# 401_RPi0.net
KiCad netlist of a schematic drawn in Altium Designer
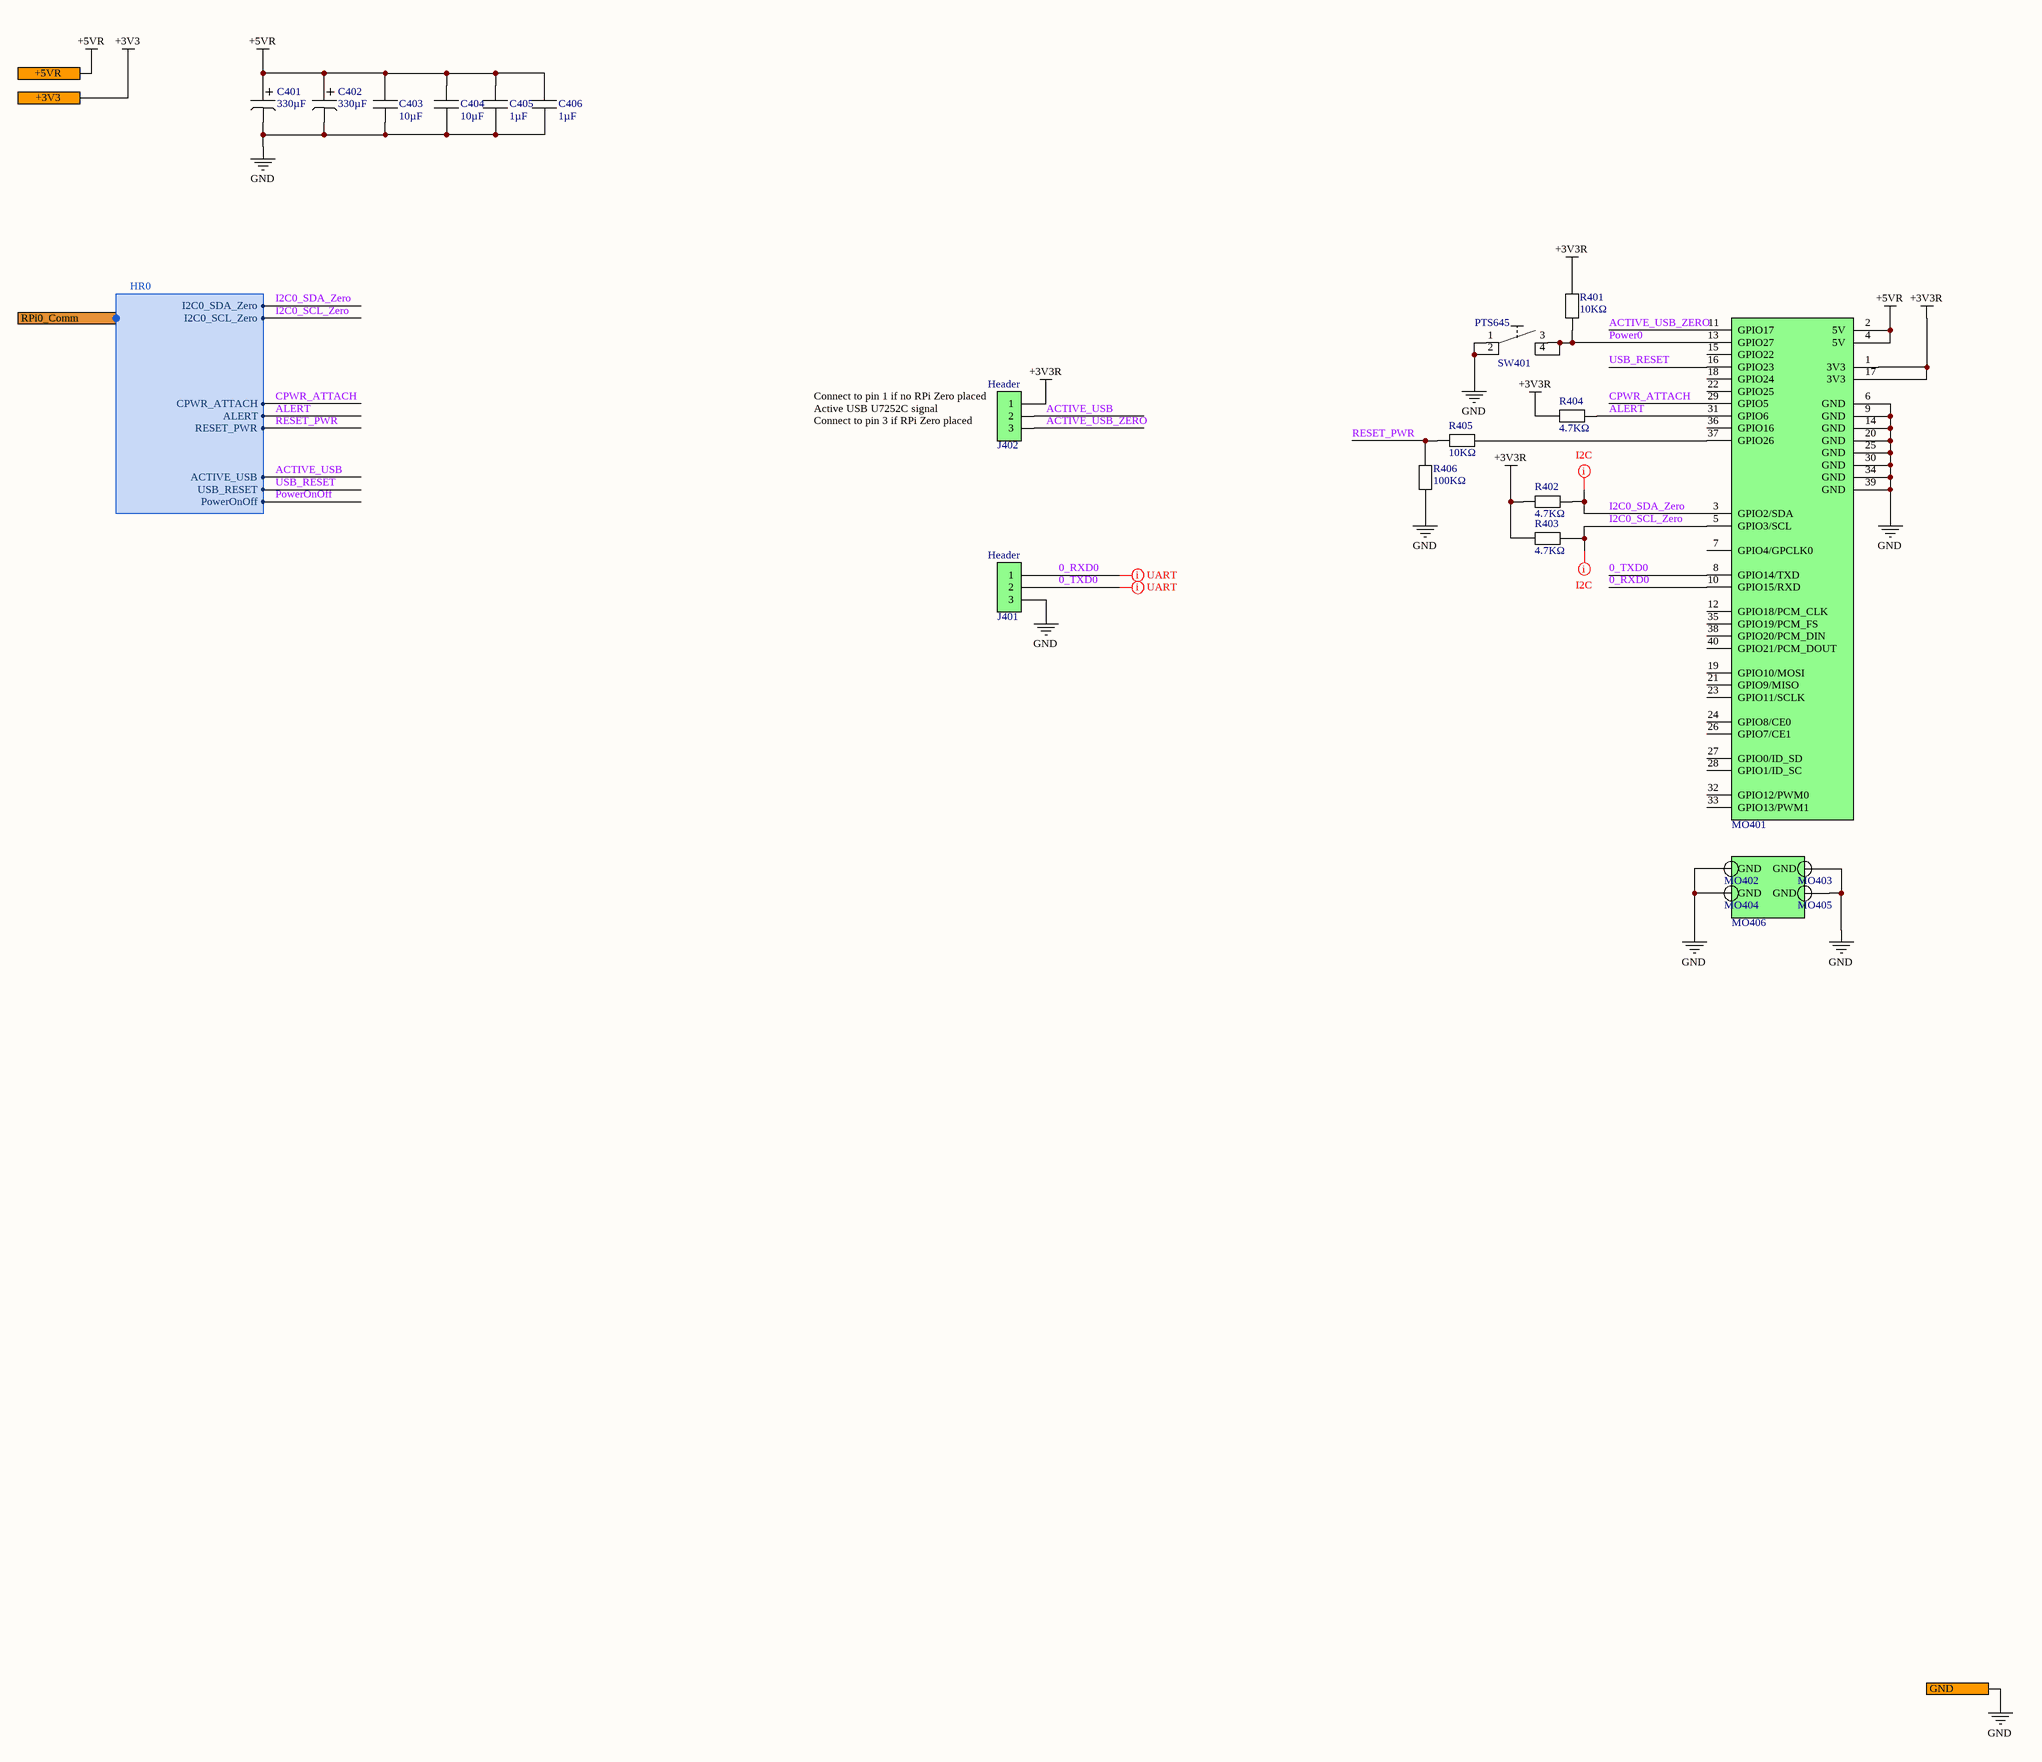
[diagram p0: 401_RPi0.SchDoc]

(export (version "E")
  (design (tool "Eeschema 10.0.6"))
  (components
    (comp (ref "C401")
      (value "330µF")
      (footprint "EC_E7")
      (description "330µF 16V 20% 16mΩ 4100mA")
      (fields
        (field (name "REFVAL") "330µF")
        (field (name "PART NUMBER") "CA0012")
        (field (name "MANFACTPART") "16SVPG330MX")
      )
      (libsource (lib "GTS_Database") (part "C+"))
    )
    (comp (ref "C402")
      (value "330µF")
      (footprint "EC_E7")
      (description "330µF 16V 20% 16mΩ 4100mA")
      (fields
        (field (name "REFVAL") "330µF")
        (field (name "PART NUMBER") "CA0012")
        (field (name "MANFACTPART") "16SVPG330MX")
      )
      (libsource (lib "GTS_Database") (part "C+"))
    )
    (comp (ref "C403")
      (value "10µF")
      (footprint "C0805")
      (description "10µF 16V 10% X5R")
      (fields
        (field (name "REFVAL") "10µF")
        (field (name "PART NUMBER") "CA0001")
        (field (name "MANFACTPART") "GRM21BR61C106KE15L")
      )
      (libsource (lib "GTS_Database") (part "C"))
    )
    (comp (ref "C404")
      (value "10µF")
      (footprint "C0805")
      (description "10µF 16V 10% X5R")
      (fields
        (field (name "REFVAL") "10µF")
        (field (name "PART NUMBER") "CA0001")
        (field (name "MANFACTPART") "GRM21BR61C106KE15L")
      )
      (libsource (lib "GTS_Database") (part "C"))
    )
    (comp (ref "C405")
      (value "1µF")
      (footprint "C0603")
      (description "1µF 16V 10% X5R")
      (fields
        (field (name "REFVAL") "1µF")
        (field (name "PART NUMBER") "CA0003")
        (field (name "MANFACTPART") "C1608X5R1C105K080AA")
      )
      (libsource (lib "GTS_Database") (part "C"))
    )
    (comp (ref "C406")
      (value "1µF")
      (footprint "C0603")
      (description "1µF 16V 10% X5R")
      (fields
        (field (name "REFVAL") "1µF")
        (field (name "PART NUMBER") "CA0003")
        (field (name "MANFACTPART") "C1608X5R1C105K080AA")
      )
      (libsource (lib "GTS_Database") (part "C"))
    )
    (comp (ref "J401")
      (value "Header")
      (footprint "1X3P_2.54mm")
      (description "Header 1x3P")
      (fields
        (field (name "REFVAL") "Header")
        (field (name "PART NUMBER") "CO0018")
        (field (name "MANFACTPART") "G800W305018EU")
      )
      (libsource (lib "GTS_Database") (part "CONN1X3P"))
    )
    (comp (ref "J402")
      (value "Header")
      (footprint "1X3P_2.54mm")
      (description "Header 1x3P")
      (fields
        (field (name "REFVAL") "Header")
        (field (name "PART NUMBER") "CO0018")
        (field (name "MANFACTPART") "G800W305018EU")
      )
      (libsource (lib "GTS_Database") (part "CONN1X3P"))
    )
    (comp (ref "MO401")
      (value "ZeroW-1")
      (footprint "RPIZeroW_HeaderPins")
      (description "RPI ZeroW Header 1-40")
      (fields (field (name "PART NUMBER") "MO0017") (field (name "MANFACTPART") "9900002236265"))
      (libsource (lib "GTS_Database") (part "RPIZeroW_Pins"))
    )
    (comp (ref "MO402")
      (value "ZeroW-M")
      (footprint "CM4-M")
      (description "RPI ZeroW Mounting Studs")
      (fields (field (name "PART NUMBER") "MO0016") (field (name "MANFACTPART") "9774030151R"))
      (libsource (lib "GTS_Database") (part "RPICM4_Mounting"))
    )
    (comp (ref "MO403")
      (value "ZeroW-M")
      (footprint "CM4-M")
      (description "RPI ZeroW Mounting Studs")
      (fields (field (name "PART NUMBER") "MO0016") (field (name "MANFACTPART") "9774030151R"))
      (libsource (lib "GTS_Database") (part "RPICM4_Mounting"))
    )
    (comp (ref "MO404")
      (value "ZeroW-M")
      (footprint "CM4-M")
      (description "RPI ZeroW Mounting Studs")
      (fields (field (name "PART NUMBER") "MO0016") (field (name "MANFACTPART") "9774030151R"))
      (libsource (lib "GTS_Database") (part "RPICM4_Mounting"))
    )
    (comp (ref "MO405")
      (value "ZeroW-M")
      (footprint "CM4-M")
      (description "RPI ZeroW Mounting Studs")
      (fields (field (name "PART NUMBER") "MO0016") (field (name "MANFACTPART") "9774030151R"))
      (libsource (lib "GTS_Database") (part "RPICM4_Mounting"))
    )
    (comp (ref "MO406")
      (value "ZeroW")
      (footprint "RPIZeroW_Layout_Heightened")
      (description "Outline of ZeroW Heigthened P\\lacement")
      (fields (field (name "PART NUMBER") "MO0022") (field (name "MANFACTPART") "RPI Zero W"))
      (libsource (lib "GTS_Database") (part "RPIZeroW_Layout"))
    )
    (comp (ref "R401")
      (value "10KΩ")
      (footprint "R0402")
      (description "10KΩ 1% 62.5mW")
      (fields
        (field (name "REFVAL") "10KΩ")
        (field (name "PART NUMBER") "RS0011")
        (field (name "MANFACTPART") "WR04X1002FTL")
      )
      (libsource (lib "GTS_Database") (part "R"))
    )
    (comp (ref "R402")
      (value "4.7KΩ")
      (footprint "R0603")
      (description "4.7KΩ 1% 100mW")
      (fields
        (field (name "REFVAL") "4.7KΩ")
        (field (name "PART NUMBER") "RS0002")
        (field (name "MANFACTPART") "WR06X4701FTL")
      )
      (libsource (lib "GTS_Database") (part "R"))
    )
    (comp (ref "R403")
      (value "4.7KΩ")
      (footprint "R0603")
      (description "4.7KΩ 1% 100mW")
      (fields
        (field (name "REFVAL") "4.7KΩ")
        (field (name "PART NUMBER") "RS0002")
        (field (name "MANFACTPART") "WR06X4701FTL")
      )
      (libsource (lib "GTS_Database") (part "R"))
    )
    (comp (ref "R404")
      (value "4.7KΩ")
      (footprint "R0603")
      (description "4.7KΩ 1% 100mW")
      (fields
        (field (name "REFVAL") "4.7KΩ")
        (field (name "PART NUMBER") "RS0002")
        (field (name "MANFACTPART") "WR06X4701FTL")
      )
      (libsource (lib "GTS_Database") (part "R"))
    )
    (comp (ref "R405")
      (value "10KΩ")
      (footprint "R0402")
      (description "10KΩ 1% 62.5mW")
      (fields
        (field (name "REFVAL") "10KΩ")
        (field (name "PART NUMBER") "RS0011")
        (field (name "MANFACTPART") "WR04X1002FTL")
      )
      (libsource (lib "GTS_Database") (part "R"))
    )
    (comp (ref "R406")
      (value "100KΩ")
      (footprint "R0402")
      (description "100KΩ 1% 62.5mW 100PPM")
      (fields
        (field (name "REFVAL") "100KΩ")
        (field (name "PART NUMBER") "RS0036")
        (field (name "MANFACTPART") "AC0402FR-13100KL")
      )
      (libsource (lib "GTS_Database") (part "R"))
    )
    (comp (ref "SW401")
      (value "PTS645")
      (footprint "PTS645-V")
      (description "TACTILE SWITCH SPST")
      (fields
        (field (name "REFVAL") "PTS645")
        (field (name "PART NUMBER") "SW0003")
        (field (name "MANFACTPART") "PTS645VK832LFS")
      )
      (libsource (lib "GTS_Database") (part "SPST-2-4"))
    )
  )
  (nets
    (net (code "3") (name "+3V3R") (class "Default")
      (node (ref "J402") (pin "1") (pinfunction "1_1") (pintype "passive"))
      (node (ref "MO401") (pin "1") (pinfunction "3V3_1") (pintype "passive"))
      (node (ref "MO401") (pin "17") (pinfunction "3V3_17") (pintype "passive"))
      (node (ref "R401") (pin "2") (pinfunction "2_2") (pintype "passive"))
      (node (ref "R402") (pin "1") (pinfunction "1_1") (pintype "passive"))
      (node (ref "R403") (pin "1") (pinfunction "1_1") (pintype "passive"))
      (node (ref "R404") (pin "1") (pinfunction "1_1") (pintype "passive"))
    )
    (net (code "4") (name "+5VR") (class "Default")
      (node (ref "C401") (pin "1") (pinfunction "1_1") (pintype "passive"))
      (node (ref "C402") (pin "1") (pinfunction "1_1") (pintype "passive"))
      (node (ref "C403") (pin "1") (pinfunction "1_1") (pintype "passive"))
      (node (ref "C404") (pin "1") (pinfunction "1_1") (pintype "passive"))
      (node (ref "C405") (pin "1") (pinfunction "1_1") (pintype "passive"))
      (node (ref "C406") (pin "1") (pinfunction "1_1") (pintype "passive"))
      (node (ref "MO401") (pin "2") (pinfunction "5V_2") (pintype "passive"))
      (node (ref "MO401") (pin "4") (pinfunction "5V_4") (pintype "passive"))
    )
    (net (code "5") (name "/0_RXD0") (class "Default")
      (node (ref "J401") (pin "1") (pinfunction "1_1") (pintype "passive"))
      (node (ref "MO401") (pin "10") (pinfunction "GPIO15/RXD_10") (pintype "passive"))
    )
    (net (code "6") (name "/0_TXD0") (class "Default")
      (node (ref "J401") (pin "2") (pinfunction "2_2") (pintype "passive"))
      (node (ref "MO401") (pin "8") (pinfunction "GPIO14/TXD_8") (pintype "passive"))
    )
    (net (code "7") (name "/ACTIVE_USB") (class "Default")
      (node (ref "J402") (pin "2") (pinfunction "2_2") (pintype "passive"))
    )
    (net (code "8") (name "/ACTIVE_USB_ZERO") (class "Default")
      (node (ref "J402") (pin "3") (pinfunction "3_3") (pintype "passive"))
      (node (ref "MO401") (pin "11") (pinfunction "GPIO17_11") (pintype "passive"))
    )
    (net (code "9") (name "/ALERT") (class "Default")
      (node (ref "MO401") (pin "31") (pinfunction "GPIO6_31") (pintype "passive"))
      (node (ref "R404") (pin "2") (pinfunction "2_2") (pintype "passive"))
    )
    (net (code "10") (name "/CPWR_ATTACH") (class "Default")
      (node (ref "MO401") (pin "29") (pinfunction "GPIO5_29") (pintype "passive"))
    )
    (net (code "11") (name "/I2C0_SCL_Zero") (class "Default")
      (node (ref "MO401") (pin "5") (pinfunction "GPIO3/SCL_5") (pintype "passive"))
      (node (ref "R403") (pin "2") (pinfunction "2_2") (pintype "passive"))
    )
    (net (code "12") (name "/I2C0_SDA_Zero") (class "Default")
      (node (ref "MO401") (pin "3") (pinfunction "GPIO2/SDA_3") (pintype "passive"))
      (node (ref "R402") (pin "2") (pinfunction "2_2") (pintype "passive"))
    )
    (net (code "13") (name "/Power0") (class "Default")
      (node (ref "MO401") (pin "13") (pinfunction "GPIO27_13") (pintype "passive"))
      (node (ref "R401") (pin "1") (pinfunction "1_1") (pintype "passive"))
      (node (ref "SW401") (pin "3") (pinfunction "3_3") (pintype "passive"))
      (node (ref "SW401") (pin "4") (pinfunction "4_4") (pintype "passive"))
    )
    (net (code "15") (name "/RESET_PWR") (class "Default")
      (node (ref "R405") (pin "1") (pinfunction "1_1") (pintype "passive"))
      (node (ref "R406") (pin "2") (pinfunction "2_2") (pintype "passive"))
    )
    (net (code "16") (name "/USB_RESET") (class "Default")
      (node (ref "MO401") (pin "16") (pinfunction "GPIO23_16") (pintype "passive"))
    )
    (net (code "18") (name "GND") (class "Default")
      (node (ref "C401") (pin "2") (pinfunction "2_2") (pintype "passive"))
      (node (ref "C402") (pin "2") (pinfunction "2_2") (pintype "passive"))
      (node (ref "C403") (pin "2") (pinfunction "2_2") (pintype "passive"))
      (node (ref "C404") (pin "2") (pinfunction "2_2") (pintype "passive"))
      (node (ref "C405") (pin "2") (pinfunction "2_2") (pintype "passive"))
      (node (ref "C406") (pin "2") (pinfunction "2_2") (pintype "passive"))
      (node (ref "J401") (pin "3") (pinfunction "3_3") (pintype "passive"))
      (node (ref "MO401") (pin "14") (pinfunction "GND_14") (pintype "passive"))
      (node (ref "MO401") (pin "20") (pinfunction "GND_20") (pintype "passive"))
      (node (ref "MO401") (pin "25") (pinfunction "GND_25") (pintype "passive"))
      (node (ref "MO401") (pin "30") (pinfunction "GND_30") (pintype "passive"))
      (node (ref "MO401") (pin "34") (pinfunction "GND_34") (pintype "passive"))
      (node (ref "MO401") (pin "39") (pinfunction "GND_39") (pintype "passive"))
      (node (ref "MO401") (pin "6") (pinfunction "GND_6") (pintype "passive"))
      (node (ref "MO401") (pin "9") (pinfunction "GND_9") (pintype "passive"))
      (node (ref "MO402") (pin "GND") (pinfunction "GND_GND") (pintype "passive"))
      (node (ref "MO403") (pin "GND") (pinfunction "GND_GND") (pintype "passive"))
      (node (ref "MO404") (pin "GND") (pinfunction "GND_GND") (pintype "passive"))
      (node (ref "MO405") (pin "GND") (pinfunction "GND_GND") (pintype "passive"))
      (node (ref "R406") (pin "1") (pinfunction "1_1") (pintype "passive"))
      (node (ref "SW401") (pin "1") (pinfunction "1_1") (pintype "passive"))
      (node (ref "SW401") (pin "2") (pinfunction "2_2") (pintype "passive"))
    )
    (net (code "19") (name "Net-(MO401-GPIO26)") (class "Default")
      (node (ref "MO401") (pin "37") (pinfunction "GPIO26_37") (pintype "passive"))
      (node (ref "R405") (pin "2") (pinfunction "2_2") (pintype "passive"))
    )
    (net (code "20") (name "unconnected-(MO401-GPIO0{slash}ID_SD-Pad27)") (class "Default")
      (node (ref "MO401") (pin "27") (pinfunction "GPIO0/ID_SD_27") (pintype "passive"))
    )
    (net (code "21") (name "unconnected-(MO401-GPIO1{slash}ID_SC-Pad28)") (class "Default")
      (node (ref "MO401") (pin "28") (pinfunction "GPIO1/ID_SC_28") (pintype "passive"))
    )
    (net (code "22") (name "unconnected-(MO401-GPIO4{slash}GPCLK0-Pad7)") (class "Default")
      (node (ref "MO401") (pin "7") (pinfunction "GPIO4/GPCLK0_7") (pintype "passive"))
    )
    (net (code "23") (name "unconnected-(MO401-GPIO7{slash}CE1-Pad26)") (class "Default")
      (node (ref "MO401") (pin "26") (pinfunction "GPIO7/CE1_26") (pintype "passive"))
    )
    (net (code "24") (name "unconnected-(MO401-GPIO8{slash}CE0-Pad24)") (class "Default")
      (node (ref "MO401") (pin "24") (pinfunction "GPIO8/CE0_24") (pintype "passive"))
    )
    (net (code "25") (name "unconnected-(MO401-GPIO9{slash}MISO-Pad21)") (class "Default")
      (node (ref "MO401") (pin "21") (pinfunction "GPIO9/MISO_21") (pintype "passive"))
    )
    (net (code "26") (name "unconnected-(MO401-GPIO10{slash}MOSI-Pad19)") (class "Default")
      (node (ref "MO401") (pin "19") (pinfunction "GPIO10/MOSI_19") (pintype "passive"))
    )
    (net (code "27") (name "unconnected-(MO401-GPIO11{slash}SCLK-Pad23)") (class "Default")
      (node (ref "MO401") (pin "23") (pinfunction "GPIO11/SCLK_23") (pintype "passive"))
    )
    (net (code "28") (name "unconnected-(MO401-GPIO12{slash}PWM0-Pad32)") (class "Default")
      (node (ref "MO401") (pin "32") (pinfunction "GPIO12/PWM0_32") (pintype "passive"))
    )
    (net (code "29") (name "unconnected-(MO401-GPIO13{slash}PWM1-Pad33)") (class "Default")
      (node (ref "MO401") (pin "33") (pinfunction "GPIO13/PWM1_33") (pintype "passive"))
    )
    (net (code "30") (name "unconnected-(MO401-GPIO16-Pad36)") (class "Default")
      (node (ref "MO401") (pin "36") (pinfunction "GPIO16_36") (pintype "passive"))
    )
    (net (code "31") (name "unconnected-(MO401-GPIO18{slash}PCM_CLK-Pad12)") (class "Default")
      (node (ref "MO401") (pin "12") (pinfunction "GPIO18/PCM_CLK_12") (pintype "passive"))
    )
    (net (code "32") (name "unconnected-(MO401-GPIO19{slash}PCM_FS-Pad35)") (class "Default")
      (node (ref "MO401") (pin "35") (pinfunction "GPIO19/PCM_FS_35") (pintype "passive"))
    )
    (net (code "33") (name "unconnected-(MO401-GPIO20{slash}PCM_DIN-Pad38)") (class "Default")
      (node (ref "MO401") (pin "38") (pinfunction "GPIO20/PCM_DIN_38") (pintype "passive"))
    )
    (net (code "34") (name "unconnected-(MO401-GPIO21{slash}PCM_DOUT-Pad40)") (class "Default")
      (node (ref "MO401") (pin "40") (pinfunction "GPIO21/PCM_DOUT_40") (pintype "passive"))
    )
    (net (code "35") (name "unconnected-(MO401-GPIO22-Pad15)") (class "Default")
      (node (ref "MO401") (pin "15") (pinfunction "GPIO22_15") (pintype "passive"))
    )
    (net (code "36") (name "unconnected-(MO401-GPIO24-Pad18)") (class "Default")
      (node (ref "MO401") (pin "18") (pinfunction "GPIO24_18") (pintype "passive"))
    )
    (net (code "37") (name "unconnected-(MO401-GPIO25-Pad22)") (class "Default")
      (node (ref "MO401") (pin "22") (pinfunction "GPIO25_22") (pintype "passive"))
    )
  )
)
